# Channel.net
KiCad netlist of a schematic drawn in Altium Designer
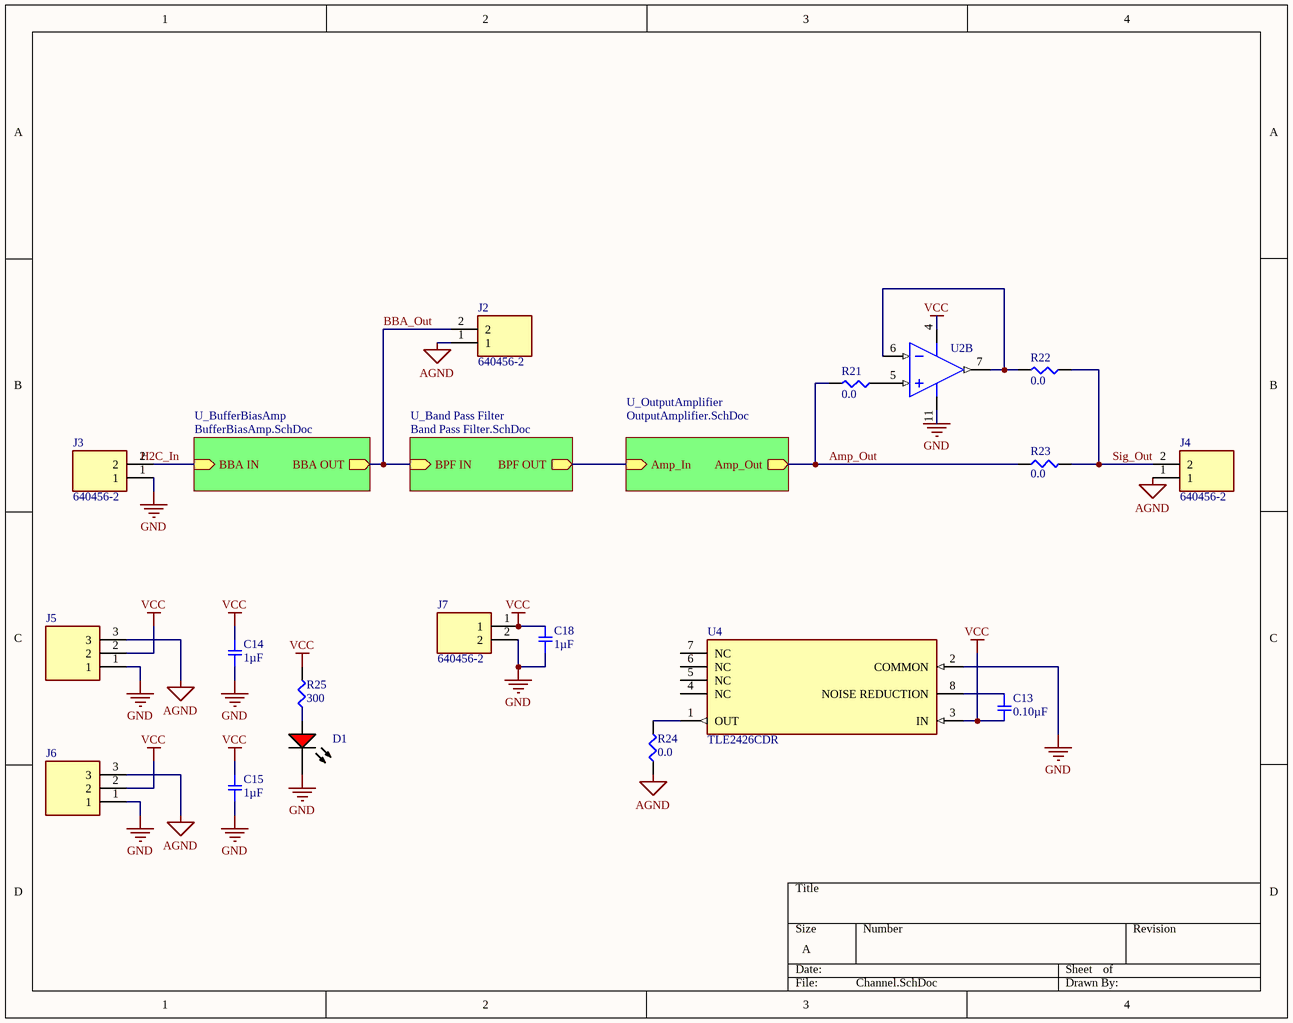
[diagram p0: Channel.SchDoc]

(export (version "E")
  (design (tool "Eeschema 10.0.6"))
  (components
    (comp (ref "C13")
      (value "0.10µF")
      (footprint "SMD-0603C")
      (description "CAP CER 0.1UF 16V X7R 0603")
      (fields
        (field (name "MANUFACTURER") "Samsung Electro-Mechanics")
        (field (name "MANUFACTURER PART NUMBER") "CL10B104KB8NNWC")
      )
      (libsource (lib "capacitor_murata_0603") (part "GCJ188R71C104KA01D"))
    )
    (comp (ref "C14")
      (value "1µF")
      (footprint "SMD-0603C")
      (description "CAP CER 1UF 16V X7R 0603")
      (fields
        (field (name "MANUFACTURER") "Samsung Electro-Mechanics")
        (field (name "MANUFACTURER PART NUMBER") "CL10A105KA8NNNC")
      )
      (libsource (lib "capacitor_murata_0603") (part "GCM188R71C105KA64D"))
    )
    (comp (ref "C15")
      (value "1µF")
      (footprint "SMD-0603C")
      (description "CAP CER 1UF 16V X7R 0603")
      (fields
        (field (name "MANUFACTURER") "Samsung Electro-Mechanics")
        (field (name "MANUFACTURER PART NUMBER") "CL10A105KA8NNNC")
      )
      (libsource (lib "capacitor_murata_0603") (part "GCM188R71C105KA64D"))
    )
    (comp (ref "C18")
      (value "1µF")
      (footprint "SMD-0603C")
      (description "CAP CER 1UF 16V X7R 0603")
      (fields
        (field (name "MANUFACTURER") "Samsung Electro-Mechanics")
        (field (name "MANUFACTURER PART NUMBER") "CL10A105KA8NNNC")
      )
      (libsource (lib "capacitor_murata_0603") (part "GCM188R71C105KA64D"))
    )
    (comp (ref "D1")
      (value "TLMS1100-GS08")
      (footprint "VISH-TLMX1100_V")
      (description "LED, RED, 2.1 V, -40 to 100 degC, 2-Pin SMD (0603), RoHS, Tape and Reel")
      (fields
        (field (name "MANUFACTURER") "Wurth Elektronics")
        (field (name "MANUFACTURER PART NUMBER") "150080SS75000")
      )
      (libsource (lib "Altium Content Vault") (part "LED-RED-AK-2"))
    )
    (comp (ref "J2")
      (value "640456-2")
      (footprint "TE_640456-2")
      (description "Connector Header Through Hole 2 position 0.100 _2.54mm_")
      (fields (field (name "MF") "TE Connectivity"))
      (libsource (lib "") (part "640456-2_1"))
    )
    (comp (ref "J3")
      (value "640456-2")
      (footprint "TE_640456-2")
      (description "Connector Header Through Hole 2 position 0.100 _2.54mm_ Keyed")
      (fields (field (name "MF") "TE Connectivity"))
      (libsource (lib "") (part "640456-2_2"))
    )
    (comp (ref "J4")
      (value "640456-2")
      (footprint "TE_640456-2")
      (description "Connector Header Through Hole 2 position 0.100 _2.54mm_")
      (fields (field (name "MF") "TE Connectivity"))
      (libsource (lib "") (part "640456-2_1"))
    )
    (comp (ref "J5")
      (value "TSW-103-07-L-S")
      (footprint "TSW-103-XX-YY-S")
      (description "1x3 2.54\" pitch")
      (libsource (lib "URC_Lib") (part "TSW-103-07-L-S"))
    )
    (comp (ref "J6")
      (value "TSW-103-07-L-S")
      (footprint "TSW-103-XX-YY-S")
      (description "1x3 2.54\" pitch")
      (libsource (lib "URC_Lib") (part "TSW-103-07-L-S"))
    )
    (comp (ref "J7")
      (value "640456-2")
      (footprint "TE_640456-2")
      (description "Connector Header Through Hole 2 position 0.100 _2.54mm_")
      (fields (field (name "MF") "TE Connectivity"))
      (libsource (lib "URC_Lib") (part "640456-2"))
    )
    (comp (ref "R21")
      (value "0.0")
      (footprint "SMD-0603-RES")
      (description "RES SMD 0.0OHM JUMPER 1/10W 0603")
      (fields
        (field (name "MANUFACTURER") "Stackpole Electronics Inc")
        (field (name "MANUFACTURER PART NUMBER") "RMCF0603ZT0R00")
      )
      (libsource (lib "Panasonic_resistor_0603") (part "ERJ-3GEY0R00V"))
    )
    (comp (ref "R22")
      (value "0.0")
      (footprint "SMD-0603-RES")
      (description "RES SMD 0.0OHM JUMPER 1/10W 0603")
      (fields
        (field (name "MANUFACTURER") "Stackpole Electronics Inc")
        (field (name "MANUFACTURER PART NUMBER") "RMCF0603ZT0R00")
      )
      (libsource (lib "Panasonic_resistor_0603") (part "ERJ-3GEY0R00V"))
    )
    (comp (ref "R23")
      (value "0.0")
      (footprint "SMD-0603-RES")
      (description "RES SMD 0.0OHM JUMPER 1/10W 0603")
      (fields
        (field (name "MANUFACTURER") "Stackpole Electronics Inc")
        (field (name "MANUFACTURER PART NUMBER") "RMCF0603ZT0R00")
      )
      (libsource (lib "Panasonic_resistor_0603") (part "ERJ-3GEY0R00V"))
    )
    (comp (ref "R24")
      (value "0.0")
      (footprint "SMD-0603-RES")
      (description "RES SMD 0.0OHM JUMPER 1/10W 0603")
      (fields
        (field (name "MANUFACTURER") "Stackpole Electronics Inc")
        (field (name "MANUFACTURER PART NUMBER") "RMCF0603ZT0R00")
      )
      (libsource (lib "Panasonic_resistor_0603") (part "ERJ-3GEY0R00V"))
    )
    (comp (ref "R25")
      (value "300")
      (footprint "SMD-0603-RES")
      (description "RES SMD 300 OHM 1% 1/10W 0603")
      (fields
        (field (name "MANUFACTURER") "Panasonic Electronic Components")
        (field (name "MANUFACTURER PART NUMBER") "ERJ-3EKF3000V")
      )
      (libsource (lib "Panasonic_resistor_0603") (part "ERJ-3EKF3000V"))
    )
    (comp (ref "U2")
      (value "OPA1604AIPWR")
      (footprint "PW0014A_N")
      (fields (field (name "MANUFACTURER") "Texas Instruments"))
      (libsource (lib "Altium Content Vault") (part "TI-OPA16X4_4XXX-14"))
    )
    (comp (ref "U4")
      (value "TLE2426CDR")
      (footprint "FP-D0008A-IPC_B")
      (description "Ground Reference (Virtual) Voltage Reference IC Adjustable 2V 20 VV ±1% 20 mA 8-SOIC")
      (fields
        (field (name "MANUFACTURER") "Texas Instruments")
        (field (name "MANUFACTURER PART NUMBER") "TLE2426MD")
      )
      (libsource (lib "Altium Content Vault") (part "6a05ed44ac4318f8a6b310f721958da"))
    )
  )
  (nets
    (net (code "1") (name "/Amp_Out") (class "Default")
      (node (ref "R21") (pin "2") (pinfunction "2_2") (pintype "passive"))
      (node (ref "R23") (pin "1") (pinfunction "1_1") (pintype "passive"))
    )
    (net (code "2") (name "/BBA IN") (class "Default")
      (node (ref "J3") (pin "2") (pinfunction "2_2") (pintype "passive"))
    )
    (net (code "3") (name "/BBA_Out") (class "Default")
      (node (ref "J2") (pin "2") (pinfunction "2_2") (pintype "passive"))
    )
    (net (code "6") (name "/Sig_Out") (class "Default")
      (node (ref "J4") (pin "2") (pinfunction "2_2") (pintype "passive"))
      (node (ref "R22") (pin "1") (pinfunction "1_1") (pintype "passive"))
      (node (ref "R23") (pin "2") (pinfunction "2_2") (pintype "passive"))
    )
    (net (code "7") (name "AGND") (class "Default")
      (node (ref "J2") (pin "1") (pinfunction "1_1") (pintype "passive"))
      (node (ref "J4") (pin "1") (pinfunction "1_1") (pintype "passive"))
      (node (ref "J5") (pin "3") (pinfunction "3_3") (pintype "passive"))
      (node (ref "J6") (pin "3") (pinfunction "3_3") (pintype "passive"))
      (node (ref "R24") (pin "1") (pinfunction "1_1") (pintype "passive"))
    )
    (net (code "8") (name "GND") (class "Default")
      (node (ref "C14") (pin "1") (pinfunction "1_1") (pintype "passive"))
      (node (ref "C15") (pin "1") (pinfunction "1_1") (pintype "passive"))
      (node (ref "C18") (pin "1") (pinfunction "1_1") (pintype "passive"))
      (node (ref "D1") (pin "2") (pinfunction "K_2") (pintype "passive"))
      (node (ref "J3") (pin "1") (pinfunction "1_1") (pintype "passive"))
      (node (ref "J5") (pin "1") (pinfunction "1_1") (pintype "passive"))
      (node (ref "J6") (pin "1") (pinfunction "1_1") (pintype "passive"))
      (node (ref "J7") (pin "2") (pinfunction "2_2") (pintype "passive"))
      (node (ref "U2") (pin "11") (pinfunction "V-_11") (pintype "power_in"))
      (node (ref "U4") (pin "2") (pinfunction "COMMON_2") (pintype "input"))
    )
    (net (code "9") (name "Net-(D1-A)") (class "Default")
      (node (ref "D1") (pin "1") (pinfunction "A_1") (pintype "passive"))
      (node (ref "R25") (pin "1") (pinfunction "1_1") (pintype "passive"))
    )
    (net (code "10") (name "Net-(U2B-IN_B+)") (class "Default")
      (node (ref "R21") (pin "1") (pinfunction "1_1") (pintype "passive"))
      (node (ref "U2") (pin "5") (pinfunction "IN_B+_5") (pintype "input"))
    )
    (net (code "11") (name "Net-(U2B-IN_B-)") (class "Default")
      (node (ref "R22") (pin "2") (pinfunction "2_2") (pintype "passive"))
      (node (ref "U2") (pin "6") (pinfunction "IN_B-_6") (pintype "input"))
      (node (ref "U2") (pin "7") (pinfunction "OUT_B_7") (pintype "output"))
    )
    (net (code "12") (name "Net-(U4-NOISE_REDUCTION)") (class "Default")
      (node (ref "C13") (pin "1") (pinfunction "1_1") (pintype "passive"))
      (node (ref "U4") (pin "8") (pinfunction "NOISE_REDUCTION_8") (pintype "passive"))
    )
    (net (code "13") (name "Net-(U4-OUT)") (class "Default")
      (node (ref "R24") (pin "2") (pinfunction "2_2") (pintype "passive"))
      (node (ref "U4") (pin "1") (pinfunction "OUT_1") (pintype "output"))
    )
    (net (code "14") (name "VCC") (class "Default")
      (node (ref "C13") (pin "2") (pinfunction "2_2") (pintype "passive"))
      (node (ref "C14") (pin "2") (pinfunction "2_2") (pintype "passive"))
      (node (ref "C15") (pin "2") (pinfunction "2_2") (pintype "passive"))
      (node (ref "C18") (pin "2") (pinfunction "2_2") (pintype "passive"))
      (node (ref "J5") (pin "2") (pinfunction "2_2") (pintype "passive"))
      (node (ref "J6") (pin "2") (pinfunction "2_2") (pintype "passive"))
      (node (ref "J7") (pin "1") (pinfunction "1_1") (pintype "passive"))
      (node (ref "R25") (pin "2") (pinfunction "2_2") (pintype "passive"))
      (node (ref "U2") (pin "4") (pinfunction "V+_4") (pintype "power_in"))
      (node (ref "U4") (pin "3") (pinfunction "IN_3") (pintype "input"))
    )
    (net (code "15") (name "unconnected-(U4-NC-Pad4)") (class "Default")
      (node (ref "U4") (pin "4") (pinfunction "NC_4") (pintype "passive"))
    )
    (net (code "16") (name "unconnected-(U4-NC-Pad5)") (class "Default")
      (node (ref "U4") (pin "5") (pinfunction "NC_5") (pintype "passive"))
    )
    (net (code "17") (name "unconnected-(U4-NC-Pad6)") (class "Default")
      (node (ref "U4") (pin "6") (pinfunction "NC_6") (pintype "passive"))
    )
    (net (code "18") (name "unconnected-(U4-NC-Pad7)") (class "Default")
      (node (ref "U4") (pin "7") (pinfunction "NC_7") (pintype "passive"))
    )
  )
)
